# ESP-WROOM-32-Breakout.net
KiCad netlist of a schematic drawn in EAGLE
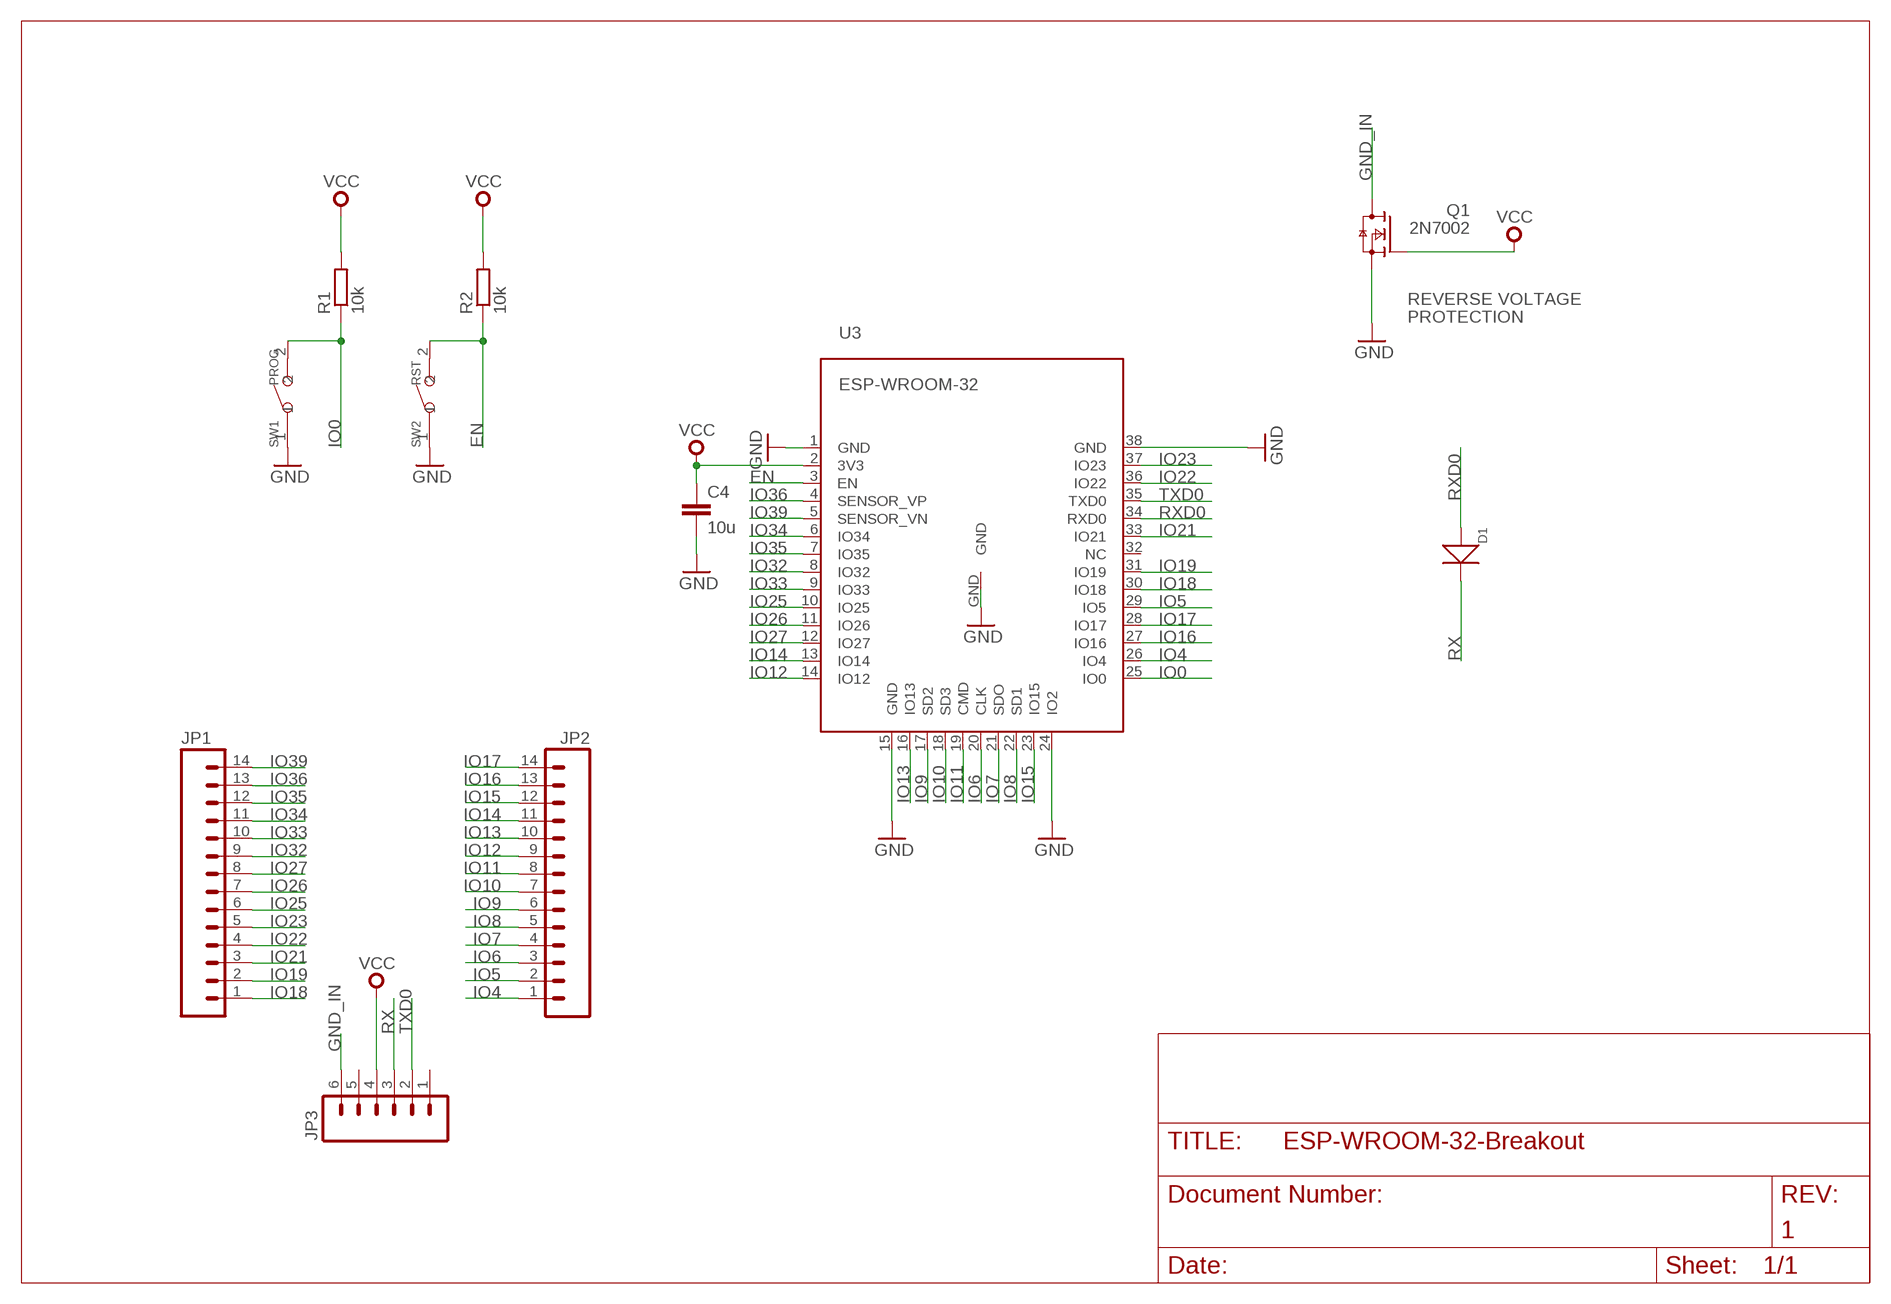
[diagram p0: schematic, sheet 1]

(export (version "E")
  (design (tool "Eeschema 10.0.6"))
  (components
    (comp (ref "C4")
      (value "10u")
      (footprint "eagle-import:C0603")
      (libsource (lib "eagle-import") (part "C-EUC0603"))
    )
    (comp (ref "D1")
      (value "DIODE'0805'")
      (footprint "eagle-import:SOD-323")
      (libsource (lib "eagle-import") (part "DIODE'0805'"))
    )
    (comp (ref "JP1")
      (value "M14")
      (footprint "eagle-import:1X14")
      (libsource (lib "eagle-import") (part "M14"))
    )
    (comp (ref "JP2")
      (value "M14")
      (footprint "eagle-import:1X14")
      (libsource (lib "eagle-import") (part "M14"))
    )
    (comp (ref "JP3")
      (value "M06SILK_FEMALE_PTH")
      (footprint "eagle-import:1X06")
      (libsource (lib "eagle-import") (part "M06SILK_FEMALE_PTH"))
    )
    (comp (ref "Q1")
      (value "2N7002")
      (footprint "eagle-import:SOT23")
      (libsource (lib "eagle-import") (part "2N7002E"))
    )
    (comp (ref "R1")
      (value "10k")
      (footprint "eagle-import:R0603")
      (libsource (lib "eagle-import") (part "R-EU_R0603"))
    )
    (comp (ref "R2")
      (value "10k")
      (footprint "eagle-import:R0603")
      (libsource (lib "eagle-import") (part "R-EU_R0603"))
    )
    (comp (ref "SW1")
      (value "PROG")
      (footprint "eagle-import:SW2-4.0-6.0X3.0X2.5MM")
      (libsource (lib "eagle-import") (part "SMD-BUTTON(2P-6.0X3.0X2.5MM)-DHT-1163S"))
    )
    (comp (ref "SW2")
      (value "RST")
      (footprint "eagle-import:SW2-4.0-6.0X3.0X2.5MM")
      (libsource (lib "eagle-import") (part "SMD-BUTTON(2P-6.0X3.0X2.5MM)-DHT-1163S"))
    )
    (comp (ref "U3")
      (value "ESP-WROOM-32")
      (footprint "eagle-import:ESP-WROOM-32")
      (libsource (lib "eagle-import") (part "ESP-WROOM-32"))
    )
  )
  (nets
    (net (code "1") (name "/EN") (class "Default")
      (node (ref "R2") (pin "1") (pinfunction "1_1") (pintype "passive"))
      (node (ref "SW2") (pin "2") (pinfunction "2_2") (pintype "bidirectional"))
      (node (ref "U3") (pin "3") (pinfunction "EN_3") (pintype "bidirectional"))
    )
    (net (code "2") (name "/GND_IN") (class "Default")
      (node (ref "JP3") (pin "6") (pinfunction "6_6") (pintype "passive"))
      (node (ref "Q1") (pin "3") (pinfunction "D_3") (pintype "passive"))
    )
    (net (code "3") (name "/IO0") (class "Default")
      (node (ref "R1") (pin "1") (pinfunction "1_1") (pintype "passive"))
      (node (ref "SW1") (pin "2") (pinfunction "2_2") (pintype "bidirectional"))
      (node (ref "U3") (pin "25") (pinfunction "IO0_25") (pintype "bidirectional"))
    )
    (net (code "4") (name "/IO4") (class "Default")
      (node (ref "JP2") (pin "1") (pinfunction "1_1") (pintype "passive"))
      (node (ref "U3") (pin "26") (pinfunction "IO4_26") (pintype "bidirectional"))
    )
    (net (code "5") (name "/IO5") (class "Default")
      (node (ref "JP2") (pin "2") (pinfunction "2_2") (pintype "passive"))
      (node (ref "U3") (pin "29") (pinfunction "IO5_29") (pintype "bidirectional"))
    )
    (net (code "6") (name "/IO6") (class "Default")
      (node (ref "JP2") (pin "3") (pinfunction "3_3") (pintype "passive"))
      (node (ref "U3") (pin "20") (pinfunction "CLK_20") (pintype "bidirectional"))
    )
    (net (code "7") (name "/IO7") (class "Default")
      (node (ref "JP2") (pin "4") (pinfunction "4_4") (pintype "passive"))
      (node (ref "U3") (pin "21") (pinfunction "SDO_21") (pintype "bidirectional"))
    )
    (net (code "8") (name "/IO8") (class "Default")
      (node (ref "JP2") (pin "5") (pinfunction "5_5") (pintype "passive"))
      (node (ref "U3") (pin "22") (pinfunction "SD1_22") (pintype "bidirectional"))
    )
    (net (code "9") (name "/IO9") (class "Default")
      (node (ref "JP2") (pin "6") (pinfunction "6_6") (pintype "passive"))
      (node (ref "U3") (pin "17") (pinfunction "SD2_17") (pintype "bidirectional"))
    )
    (net (code "10") (name "/IO10") (class "Default")
      (node (ref "JP2") (pin "7") (pinfunction "7_7") (pintype "passive"))
      (node (ref "U3") (pin "18") (pinfunction "SD3_18") (pintype "bidirectional"))
    )
    (net (code "11") (name "/IO11") (class "Default")
      (node (ref "JP2") (pin "8") (pinfunction "8_8") (pintype "passive"))
      (node (ref "U3") (pin "19") (pinfunction "CMD_19") (pintype "bidirectional"))
    )
    (net (code "12") (name "/IO12") (class "Default")
      (node (ref "JP2") (pin "9") (pinfunction "9_9") (pintype "passive"))
      (node (ref "U3") (pin "14") (pinfunction "IO12_14") (pintype "bidirectional"))
    )
    (net (code "13") (name "/IO13") (class "Default")
      (node (ref "JP2") (pin "10") (pinfunction "10_10") (pintype "passive"))
      (node (ref "U3") (pin "16") (pinfunction "IO13_16") (pintype "bidirectional"))
    )
    (net (code "14") (name "/IO14") (class "Default")
      (node (ref "JP2") (pin "11") (pinfunction "11_11") (pintype "passive"))
      (node (ref "U3") (pin "13") (pinfunction "IO14_13") (pintype "bidirectional"))
    )
    (net (code "15") (name "/IO15") (class "Default")
      (node (ref "JP2") (pin "12") (pinfunction "12_12") (pintype "passive"))
      (node (ref "U3") (pin "23") (pinfunction "IO15_23") (pintype "bidirectional"))
    )
    (net (code "16") (name "/IO16") (class "Default")
      (node (ref "JP2") (pin "13") (pinfunction "13_13") (pintype "passive"))
      (node (ref "U3") (pin "27") (pinfunction "IO16_27") (pintype "bidirectional"))
    )
    (net (code "17") (name "/IO17") (class "Default")
      (node (ref "JP2") (pin "14") (pinfunction "14_14") (pintype "passive"))
      (node (ref "U3") (pin "28") (pinfunction "IO17_28") (pintype "bidirectional"))
    )
    (net (code "18") (name "/IO18") (class "Default")
      (node (ref "JP1") (pin "1") (pinfunction "1_1") (pintype "passive"))
      (node (ref "U3") (pin "30") (pinfunction "IO18_30") (pintype "bidirectional"))
    )
    (net (code "19") (name "/IO19") (class "Default")
      (node (ref "JP1") (pin "2") (pinfunction "2_2") (pintype "passive"))
      (node (ref "U3") (pin "31") (pinfunction "IO19_31") (pintype "bidirectional"))
    )
    (net (code "20") (name "/IO21") (class "Default")
      (node (ref "JP1") (pin "3") (pinfunction "3_3") (pintype "passive"))
      (node (ref "U3") (pin "33") (pinfunction "IO21_33") (pintype "bidirectional"))
    )
    (net (code "21") (name "/IO22") (class "Default")
      (node (ref "JP1") (pin "4") (pinfunction "4_4") (pintype "passive"))
      (node (ref "U3") (pin "36") (pinfunction "IO22_36") (pintype "bidirectional"))
    )
    (net (code "22") (name "/IO23") (class "Default")
      (node (ref "JP1") (pin "5") (pinfunction "5_5") (pintype "passive"))
      (node (ref "U3") (pin "37") (pinfunction "IO23_37") (pintype "bidirectional"))
    )
    (net (code "23") (name "/IO25") (class "Default")
      (node (ref "JP1") (pin "6") (pinfunction "6_6") (pintype "passive"))
      (node (ref "U3") (pin "10") (pinfunction "IO25_10") (pintype "bidirectional"))
    )
    (net (code "24") (name "/IO26") (class "Default")
      (node (ref "JP1") (pin "7") (pinfunction "7_7") (pintype "passive"))
      (node (ref "U3") (pin "11") (pinfunction "IO26_11") (pintype "bidirectional"))
    )
    (net (code "25") (name "/IO27") (class "Default")
      (node (ref "JP1") (pin "8") (pinfunction "8_8") (pintype "passive"))
      (node (ref "U3") (pin "12") (pinfunction "IO27_12") (pintype "bidirectional"))
    )
    (net (code "26") (name "/IO32") (class "Default")
      (node (ref "JP1") (pin "9") (pinfunction "9_9") (pintype "passive"))
      (node (ref "U3") (pin "8") (pinfunction "IO32_8") (pintype "bidirectional"))
    )
    (net (code "27") (name "/IO33") (class "Default")
      (node (ref "JP1") (pin "10") (pinfunction "10_10") (pintype "passive"))
      (node (ref "U3") (pin "9") (pinfunction "IO33_9") (pintype "bidirectional"))
    )
    (net (code "28") (name "/IO34") (class "Default")
      (node (ref "JP1") (pin "11") (pinfunction "11_11") (pintype "passive"))
      (node (ref "U3") (pin "6") (pinfunction "IO34_6") (pintype "bidirectional"))
    )
    (net (code "29") (name "/IO35") (class "Default")
      (node (ref "JP1") (pin "12") (pinfunction "12_12") (pintype "passive"))
      (node (ref "U3") (pin "7") (pinfunction "IO35_7") (pintype "bidirectional"))
    )
    (net (code "30") (name "/IO36") (class "Default")
      (node (ref "JP1") (pin "13") (pinfunction "13_13") (pintype "passive"))
      (node (ref "U3") (pin "4") (pinfunction "SENSOR_VP_4") (pintype "bidirectional"))
    )
    (net (code "31") (name "/IO39") (class "Default")
      (node (ref "JP1") (pin "14") (pinfunction "14_14") (pintype "passive"))
      (node (ref "U3") (pin "5") (pinfunction "SENSOR_VN_5") (pintype "bidirectional"))
    )
    (net (code "32") (name "/RX") (class "Default")
      (node (ref "D1") (pin "-") (pinfunction "-_-") (pintype "passive"))
      (node (ref "JP3") (pin "3") (pinfunction "3_3") (pintype "passive"))
    )
    (net (code "33") (name "/RXD0") (class "Default")
      (node (ref "D1") (pin "+") (pinfunction "+_+") (pintype "passive"))
      (node (ref "U3") (pin "34") (pinfunction "RXD0_34") (pintype "bidirectional"))
    )
    (net (code "34") (name "/TXD0") (class "Default")
      (node (ref "JP3") (pin "2") (pinfunction "2_2") (pintype "passive"))
      (node (ref "U3") (pin "35") (pinfunction "TXD0_35") (pintype "bidirectional"))
    )
    (net (code "35") (name "GND") (class "Default")
      (node (ref "C4") (pin "2") (pinfunction "2_2") (pintype "passive"))
      (node (ref "Q1") (pin "2") (pinfunction "S_2") (pintype "passive"))
      (node (ref "SW1") (pin "1") (pinfunction "1_1") (pintype "bidirectional"))
      (node (ref "SW2") (pin "1") (pinfunction "1_1") (pintype "bidirectional"))
      (node (ref "U3") (pin "1") (pinfunction "GND_1") (pintype "bidirectional"))
      (node (ref "U3") (pin "15") (pinfunction "GND_15") (pintype "bidirectional"))
      (node (ref "U3") (pin "24") (pinfunction "IO2_24") (pintype "bidirectional"))
      (node (ref "U3") (pin "38") (pinfunction "GND_38") (pintype "bidirectional"))
      (node (ref "U3") (pin "GND") (pinfunction "GND_GND") (pintype "bidirectional"))
    )
    (net (code "36") (name "VCC") (class "Default")
      (node (ref "C4") (pin "1") (pinfunction "1_1") (pintype "passive"))
      (node (ref "JP3") (pin "4") (pinfunction "4_4") (pintype "passive"))
      (node (ref "Q1") (pin "1") (pinfunction "G_1") (pintype "passive"))
      (node (ref "R1") (pin "2") (pinfunction "2_2") (pintype "passive"))
      (node (ref "R2") (pin "2") (pinfunction "2_2") (pintype "passive"))
      (node (ref "U3") (pin "2") (pinfunction "3V3_2") (pintype "bidirectional"))
    )
    (net (code "37") (name "unconnected-(JP3-Pad1)") (class "Default")
      (node (ref "JP3") (pin "1") (pinfunction "1_1") (pintype "passive"))
    )
    (net (code "38") (name "unconnected-(JP3-Pad5)") (class "Default")
      (node (ref "JP3") (pin "5") (pinfunction "5_5") (pintype "passive"))
    )
    (net (code "39") (name "unconnected-(U3-NC-Pad32)") (class "Default")
      (node (ref "U3") (pin "32") (pinfunction "NC_32") (pintype "bidirectional"))
    )
  )
)
